# 2_-PHY.net
KiCad netlist of a schematic drawn in Altium Designer
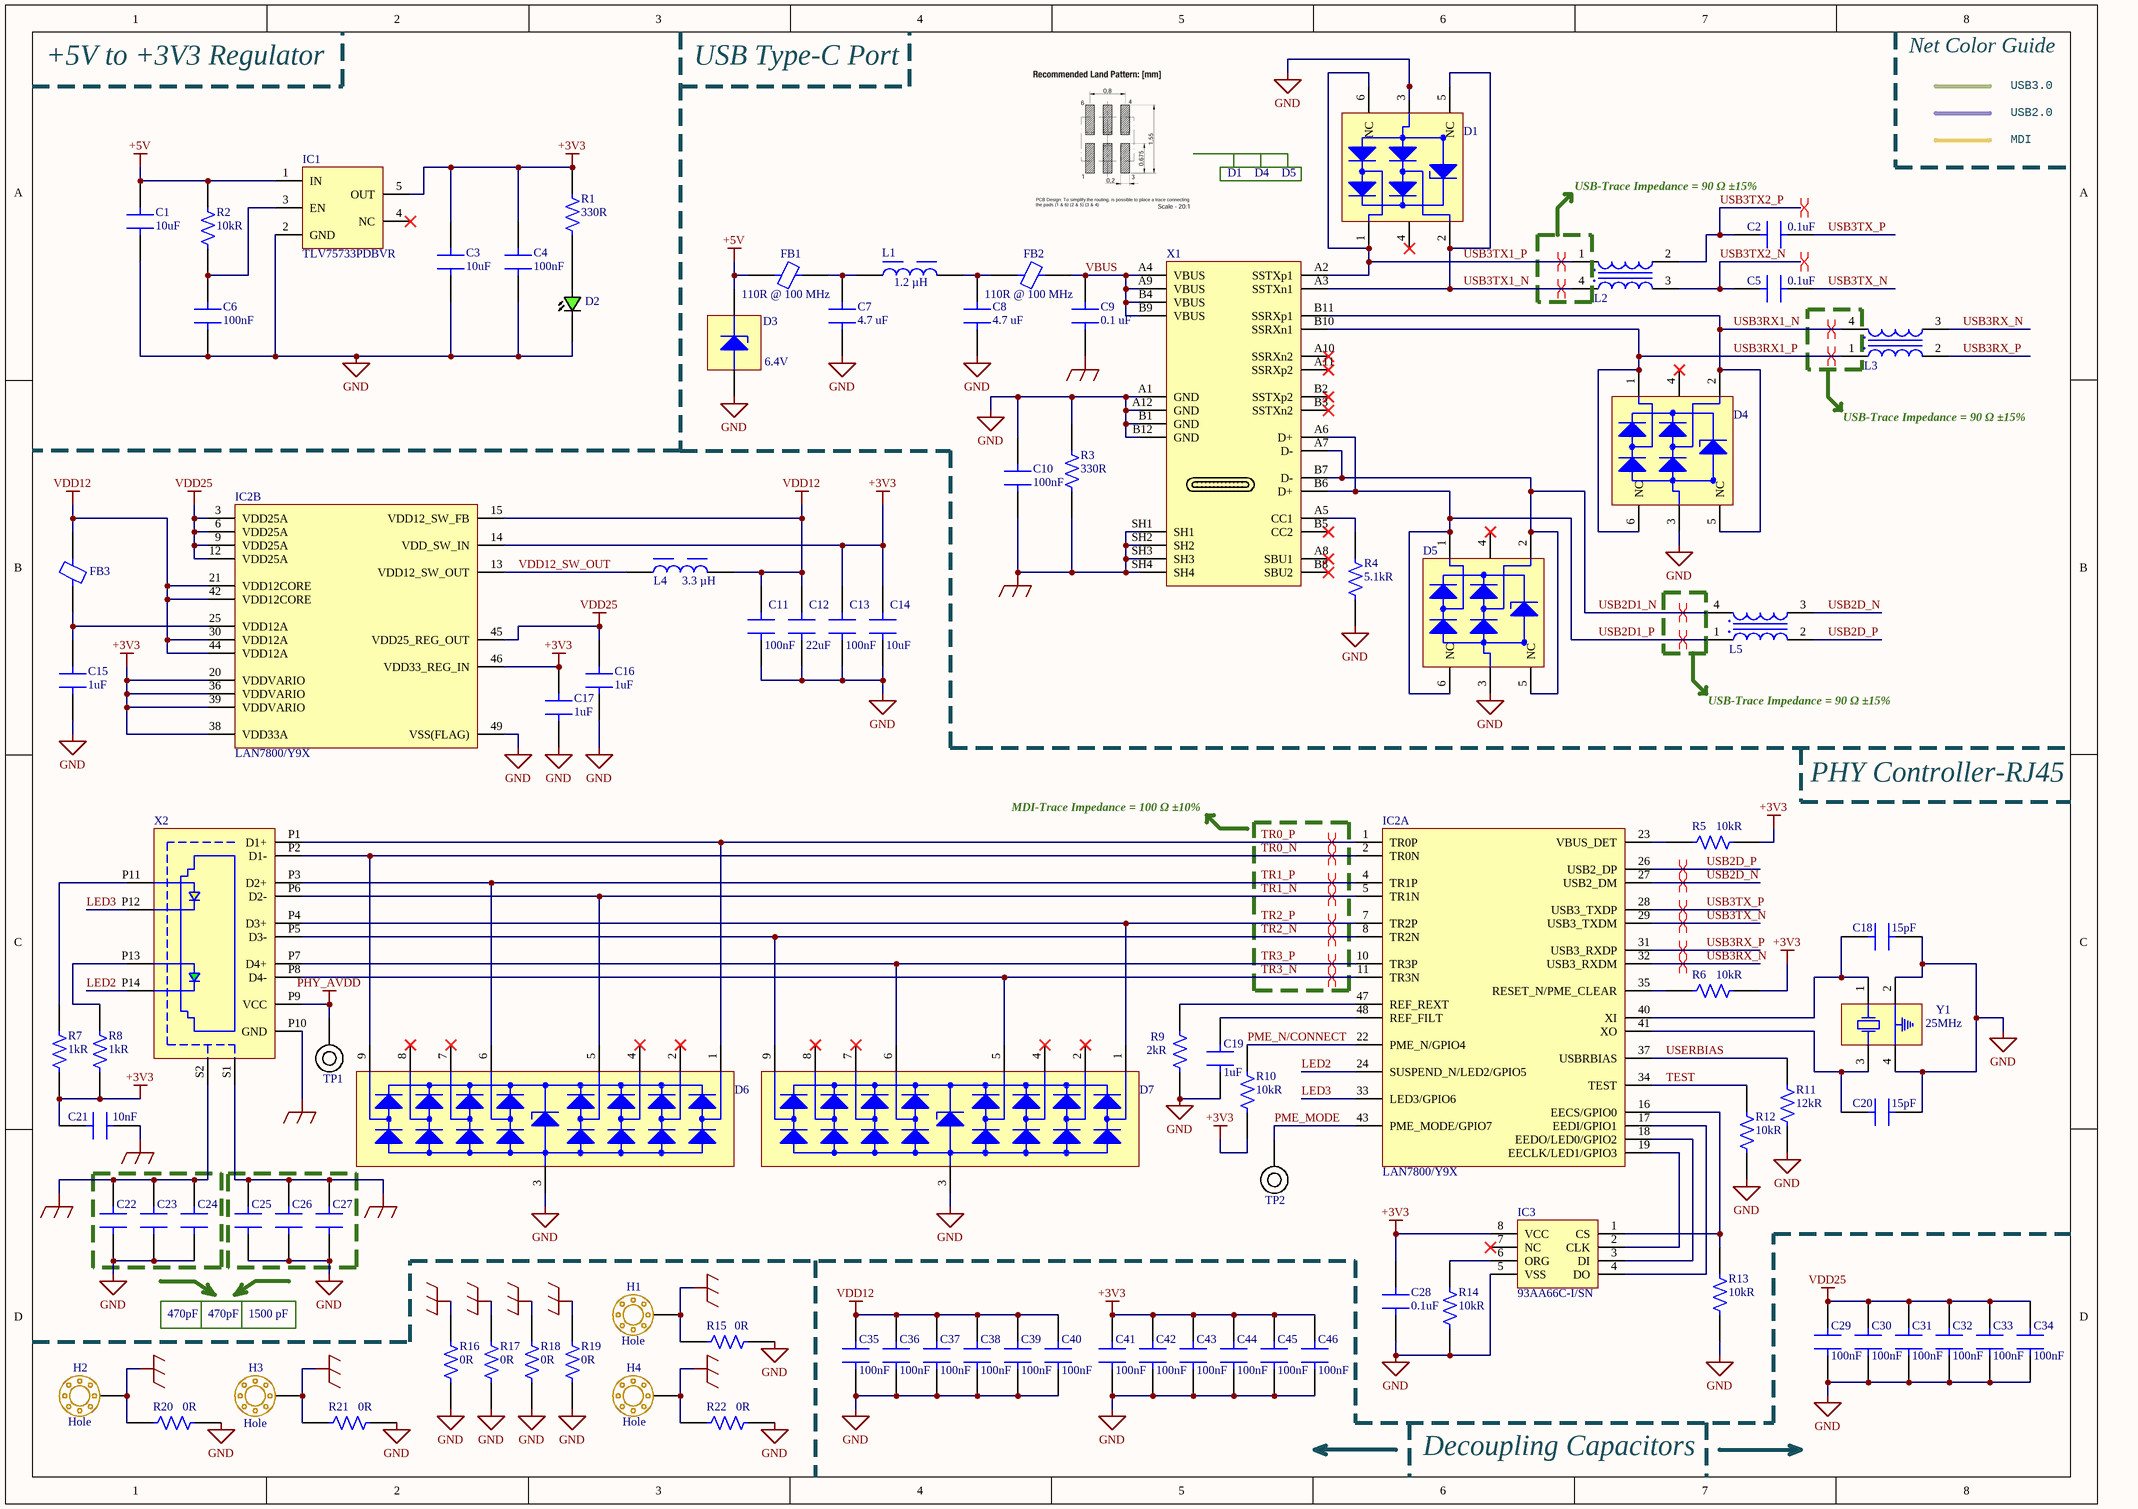
[diagram p0: [2]-PHY.SchDoc]

(export (version "E")
  (design (tool "Eeschema 10.0.6"))
  (components
    (comp (ref "C1")
      (value "GRM188R61A106ME69D")
      (footprint "CAP CER 0603 MURATA")
      (description "10 µF ±20% 10V Ceramic Capacitor X5R 0603 (1608 Metric)")
      (fields
        (field (name "MANUFACTURER") "Murata Electronics")
        (field (name "TOLERANCE") "±20%")
        (field (name "CAPACITANCE") "10uF")
        (field (name "DESIGNED BY") "ADAK")
      )
      (libsource (lib "Project_Library") (part "CAP CER 10UF 10V"))
    )
    (comp (ref "C2")
      (value "885012105018")
      (footprint "CAP CER 0402 (1005 Metric)")
      (description "0.1 µF ±20% 25V Ceramic Capacitor X5R 0402 (1005 Metric)")
      (fields
        (field (name "MANUFACTURER") "Würth Elektronik")
        (field (name "TOLERANCE") "±20%")
        (field (name "CAPACITANCE") "0.1uF")
        (field (name "DESIGNED BY") "ADAK")
      )
      (libsource (lib "Project_Library") (part "CAP CER 0.1UF 25V 0402"))
    )
    (comp (ref "C3")
      (value "GRM188R61A106ME69D")
      (footprint "CAP CER 0603 MURATA")
      (description "10 µF ±20% 10V Ceramic Capacitor X5R 0603 (1608 Metric)")
      (fields
        (field (name "MANUFACTURER") "Murata Electronics")
        (field (name "TOLERANCE") "±20%")
        (field (name "CAPACITANCE") "10uF")
        (field (name "DESIGNED BY") "ADAK")
      )
      (libsource (lib "Project_Library") (part "CAP CER 10UF 10V"))
    )
    (comp (ref "C4")
      (value "885012206071")
      (footprint "CAP CER 0603 (1608 Metric)")
      (description "0.1 µF ±10% 25V Ceramic Capacitor X7R 0603 (1608 Metric)")
      (fields
        (field (name "MANUFACTURER") "Würth Elektronik")
        (field (name "TOLERANCE") "±10%")
        (field (name "CAPACITANCE") "100nF")
        (field (name "DESIGNED BY") "ADAK")
      )
      (libsource (lib "Project_Library") (part "CAP CER 0.1UF 25V"))
    )
    (comp (ref "C5")
      (value "885012105018")
      (footprint "CAP CER 0402 (1005 Metric)")
      (description "0.1 µF ±20% 25V Ceramic Capacitor X5R 0402 (1005 Metric)")
      (fields
        (field (name "MANUFACTURER") "Würth Elektronik")
        (field (name "TOLERANCE") "±20%")
        (field (name "CAPACITANCE") "0.1uF")
        (field (name "DESIGNED BY") "ADAK")
      )
      (libsource (lib "Project_Library") (part "CAP CER 0.1UF 25V 0402"))
    )
    (comp (ref "C6")
      (value "885012206071")
      (footprint "CAP CER 0603 (1608 Metric)")
      (description "0.1 µF ±10% 25V Ceramic Capacitor X7R 0603 (1608 Metric)")
      (fields
        (field (name "MANUFACTURER") "Würth Elektronik")
        (field (name "TOLERANCE") "±10%")
        (field (name "CAPACITANCE") "100nF")
        (field (name "DESIGNED BY") "ADAK")
      )
      (libsource (lib "Project_Library") (part "CAP CER 0.1UF 25V"))
    )
    (comp (ref "C7")
      (value "885012107018")
      (footprint "CAP CER 0805 (2012 Metric)")
      (description "4.7 µF ±20% 25V Ceramic Capacitor X5R 0805 (2012 Metric)")
      (fields
        (field (name "MANUFACTURER") "Würth Elektronik")
        (field (name "TOLERANCE") "±20%")
        (field (name "CAPACITANCE") "4.7 uF")
        (field (name "DESIGNED BY") "ADAK")
      )
      (libsource (lib "Project_Library") (part "CAP CER 4.7UF 25V"))
    )
    (comp (ref "C8")
      (value "885012107018")
      (footprint "CAP CER 0805 (2012 Metric)")
      (description "4.7 µF ±20% 25V Ceramic Capacitor X5R 0805 (2012 Metric)")
      (fields
        (field (name "MANUFACTURER") "Würth Elektronik")
        (field (name "TOLERANCE") "±20%")
        (field (name "CAPACITANCE") "4.7 uF")
        (field (name "DESIGNED BY") "ADAK")
      )
      (libsource (lib "Project_Library") (part "CAP CER 4.7UF 25V"))
    )
    (comp (ref "C9")
      (value "885012207098")
      (footprint "CAP CER 0805 (2012 Metric)")
      (description "0.1 µF ±10% 50V Ceramic Capacitor X7R 0805 (2012 Metric)")
      (fields
        (field (name "MANUFACTURER") "Würth Elektronik")
        (field (name "TOLERANCE") "±10%")
        (field (name "CAPACITANCE") "0.1 uF")
        (field (name "DESIGNED BY") "ADAK")
      )
      (libsource (lib "Project_Library") (part "CAP CER 0.1UF 50V"))
    )
    (comp (ref "C10")
      (value "885012206071")
      (footprint "CAP CER 0603 (1608 Metric)")
      (description "0.1 µF ±10% 25V Ceramic Capacitor X7R 0603 (1608 Metric)")
      (fields
        (field (name "MANUFACTURER") "Würth Elektronik")
        (field (name "TOLERANCE") "±10%")
        (field (name "CAPACITANCE") "100nF")
        (field (name "DESIGNED BY") "ADAK")
      )
      (libsource (lib "Project_Library") (part "CAP CER 0.1UF 25V"))
    )
    (comp (ref "C11")
      (value "885012206071")
      (footprint "CAP CER 0603 (1608 Metric)")
      (description "0.1 µF ±10% 25V Ceramic Capacitor X7R 0603 (1608 Metric)")
      (fields
        (field (name "MANUFACTURER") "Würth Elektronik")
        (field (name "TOLERANCE") "±10%")
        (field (name "CAPACITANCE") "100nF")
        (field (name "DESIGNED BY") "ADAK")
      )
      (libsource (lib "Project_Library") (part "CAP CER 0.1UF 25V"))
    )
    (comp (ref "C12")
      (value "885012107005")
      (footprint "CAP CER 0805 (2012 Metric)")
      (description "22 µF ±20% 6.3V Ceramic Capacitor X5R 0805 (2012 Metric)")
      (fields
        (field (name "MANUFACTURER") "Würth Elektronik")
        (field (name "TOLERANCE") "±20%")
        (field (name "CAPACITANCE") "22uF")
        (field (name "DESIGNED BY") "ADAK")
      )
      (libsource (lib "Project_Library") (part "CAP CER 22UF 6.3V"))
    )
    (comp (ref "C13")
      (value "885012206071")
      (footprint "CAP CER 0603 (1608 Metric)")
      (description "0.1 µF ±10% 25V Ceramic Capacitor X7R 0603 (1608 Metric)")
      (fields
        (field (name "MANUFACTURER") "Würth Elektronik")
        (field (name "TOLERANCE") "±10%")
        (field (name "CAPACITANCE") "100nF")
        (field (name "DESIGNED BY") "ADAK")
      )
      (libsource (lib "Project_Library") (part "CAP CER 0.1UF 25V"))
    )
    (comp (ref "C14")
      (value "GRM188R61A106ME69D")
      (footprint "CAP CER 0603 MURATA")
      (description "10 µF ±20% 10V Ceramic Capacitor X5R 0603 (1608 Metric)")
      (fields
        (field (name "MANUFACTURER") "Murata Electronics")
        (field (name "TOLERANCE") "±20%")
        (field (name "CAPACITANCE") "10uF")
        (field (name "DESIGNED BY") "ADAK")
      )
      (libsource (lib "Project_Library") (part "CAP CER 10UF 10V"))
    )
    (comp (ref "C15")
      (value "885012206052")
      (footprint "CAP CER 0603 (1608 Metric)")
      (description "1 µF ±10% 16V Ceramic Capacitor X7R 0603 (1608 Metric)")
      (fields
        (field (name "MANUFACTURER") "Würth Elektronik")
        (field (name "TOLERANCE") "±10%")
        (field (name "CAPACITANCE") "1uF")
        (field (name "DESIGNED BY") "ADAK")
      )
      (libsource (lib "Project_Library") (part "CAP CER 1UF 16V 0603"))
    )
    (comp (ref "C16")
      (value "885012206052")
      (footprint "CAP CER 0603 (1608 Metric)")
      (description "1 µF ±10% 16V Ceramic Capacitor X7R 0603 (1608 Metric)")
      (fields
        (field (name "MANUFACTURER") "Würth Elektronik")
        (field (name "TOLERANCE") "±10%")
        (field (name "CAPACITANCE") "1uF")
        (field (name "DESIGNED BY") "ADAK")
      )
      (libsource (lib "Project_Library") (part "CAP CER 1UF 16V 0603"))
    )
    (comp (ref "C17")
      (value "885012206052")
      (footprint "CAP CER 0603 (1608 Metric)")
      (description "1 µF ±10% 16V Ceramic Capacitor X7R 0603 (1608 Metric)")
      (fields
        (field (name "MANUFACTURER") "Würth Elektronik")
        (field (name "TOLERANCE") "±10%")
        (field (name "CAPACITANCE") "1uF")
        (field (name "DESIGNED BY") "ADAK")
      )
      (libsource (lib "Project_Library") (part "CAP CER 1UF 16V 0603"))
    )
    (comp (ref "C18")
      (value "885012005056")
      (footprint "CAP CER 0402 (1005 Metric)")
      (description "15 pF ±5% 50V Ceramic Capacitor C0G, NP0 0402 (1005 Metric)")
      (fields
        (field (name "MANUFACTURER") "Würth Elektronik")
        (field (name "TOLERANCE") "±5%")
        (field (name "CAPACITANCE") "15pF")
        (field (name "DESIGNED BY") "ADAK")
      )
      (libsource (lib "Project_Library") (part "CAP CER 15PF 50V"))
    )
    (comp (ref "C19")
      (value "885012206052")
      (footprint "CAP CER 0603 (1608 Metric)")
      (description "1 µF ±10% 16V Ceramic Capacitor X7R 0603 (1608 Metric)")
      (fields
        (field (name "MANUFACTURER") "Würth Elektronik")
        (field (name "TOLERANCE") "±10%")
        (field (name "CAPACITANCE") "1uF")
        (field (name "DESIGNED BY") "ADAK")
      )
      (libsource (lib "Project_Library") (part "CAP CER 1UF 16V 0603"))
    )
    (comp (ref "C20")
      (value "885012005056")
      (footprint "CAP CER 0402 (1005 Metric)")
      (description "15 pF ±5% 50V Ceramic Capacitor C0G, NP0 0402 (1005 Metric)")
      (fields
        (field (name "MANUFACTURER") "Würth Elektronik")
        (field (name "TOLERANCE") "±5%")
        (field (name "CAPACITANCE") "15pF")
        (field (name "DESIGNED BY") "ADAK")
      )
      (libsource (lib "Project_Library") (part "CAP CER 15PF 50V"))
    )
    (comp (ref "C21")
      (value "885012206065")
      (footprint "CAP CER 0603 (1608 Metric)")
      (description "10000 pF ±10% 25V Ceramic Capacitor X7R 0603 (1608 Metric)")
      (fields
        (field (name "MANUFACTURER") "Würth Elektronik")
        (field (name "TOLERANCE") "±10%")
        (field (name "CAPACITANCE") "10nF")
        (field (name "DESIGNED BY") "ADAK")
      )
      (libsource (lib "Project_Library") (part "CAP CER 10000PF 25V"))
    )
    (comp (ref "C22")
      (value "885342208023")
      (footprint "CAP CER 1206 (3216 Metric)")
      (description "470 pF ±10% 2000V (2kV) Ceramic Capacitor X7R 1206 (3216 Metric)")
      (fields
        (field (name "MANUFACTURER") "Würth Elektronik")
        (field (name "TOLERANCE") "±10%")
        (field (name "CAPACITANCE") "470pF")
        (field (name "DESIGNED BY") "ADAK")
      )
      (libsource (lib "Project_Library") (part "CAP CER 470PF 2000V"))
    )
    (comp (ref "C23")
      (value "885342208023")
      (footprint "CAP CER 1206 (3216 Metric)")
      (description "470 pF ±10% 2000V (2kV) Ceramic Capacitor X7R 1206 (3216 Metric)")
      (fields
        (field (name "MANUFACTURER") "Würth Elektronik")
        (field (name "TOLERANCE") "±10%")
        (field (name "CAPACITANCE") "470pF")
        (field (name "DESIGNED BY") "ADAK")
      )
      (libsource (lib "Project_Library") (part "CAP CER 470PF 2000V"))
    )
    (comp (ref "C24")
      (value "HV1825Y152KXMATHV")
      (footprint "CAP CER 1825 (4564 Metric)")
      (description "CAP CER 1500PF 5KV X7R 1825")
      (fields
        (field (name "MANUFACTURER") "Vishay Vitramon")
        (field (name "TOLERANCE") "±10%")
        (field (name "CAPACITANCE") "1500 pF")
        (field (name "DESIGNED BY") "ADAK")
      )
      (libsource (lib "Project_Library") (part "CAP CER 1500PF 5KV"))
    )
    (comp (ref "C25")
      (value "885342208023")
      (footprint "CAP CER 1206 (3216 Metric)")
      (description "470 pF ±10% 2000V (2kV) Ceramic Capacitor X7R 1206 (3216 Metric)")
      (fields
        (field (name "MANUFACTURER") "Würth Elektronik")
        (field (name "TOLERANCE") "±10%")
        (field (name "DESIGNED BY") "ADAK")
      )
      (libsource (lib "Project_Library") (part "CAP CER 470PF 2000V"))
    )
    (comp (ref "C26")
      (value "885342208023")
      (footprint "CAP CER 1206 (3216 Metric)")
      (description "470 pF ±10% 2000V (2kV) Ceramic Capacitor X7R 1206 (3216 Metric)")
      (fields
        (field (name "MANUFACTURER") "Würth Elektronik")
        (field (name "TOLERANCE") "±10%")
        (field (name "DESIGNED BY") "ADAK")
      )
      (libsource (lib "Project_Library") (part "CAP CER 470PF 2000V"))
    )
    (comp (ref "C27")
      (value "HV1825Y152KXMATHV")
      (footprint "CAP CER 1825 (4564 Metric)")
      (description "CAP CER 1500PF 5KV X7R 1825")
      (fields
        (field (name "MANUFACTURER") "Vishay Vitramon")
        (field (name "TOLERANCE") "±10%")
        (field (name "DESIGNED BY") "ADAK")
      )
      (libsource (lib "Project_Library") (part "CAP CER 1500PF 5KV"))
    )
    (comp (ref "C28")
      (value "885012206071")
      (footprint "CAP CER 0603 (1608 Metric)")
      (description "0.1 µF ±10% 25V Ceramic Capacitor X7R 0603 (1608 Metric)")
      (fields
        (field (name "MANUFACTURER") "Würth Elektronik")
        (field (name "TOLERANCE") "±10%")
        (field (name "CAPACITANCE") "0.1uF")
        (field (name "DESIGNED BY") "ADAK")
      )
      (libsource (lib "Project_Library") (part "CAP CER 0.1UF 25V"))
    )
    (comp (ref "C29")
      (value "885012206071")
      (footprint "CAP CER 0603 (1608 Metric)")
      (description "0.1 µF ±10% 25V Ceramic Capacitor X7R 0603 (1608 Metric)")
      (fields
        (field (name "MANUFACTURER") "Würth Elektronik")
        (field (name "TOLERANCE") "±10%")
        (field (name "CAPACITANCE") "100nF")
        (field (name "DESIGNED BY") "ADAK")
      )
      (libsource (lib "Project_Library") (part "CAP CER 0.1UF 25V"))
    )
    (comp (ref "C30")
      (value "885012206071")
      (footprint "CAP CER 0603 (1608 Metric)")
      (description "0.1 µF ±10% 25V Ceramic Capacitor X7R 0603 (1608 Metric)")
      (fields
        (field (name "MANUFACTURER") "Würth Elektronik")
        (field (name "TOLERANCE") "±10%")
        (field (name "CAPACITANCE") "100nF")
        (field (name "DESIGNED BY") "ADAK")
      )
      (libsource (lib "Project_Library") (part "CAP CER 0.1UF 25V"))
    )
    (comp (ref "C31")
      (value "885012206071")
      (footprint "CAP CER 0603 (1608 Metric)")
      (description "0.1 µF ±10% 25V Ceramic Capacitor X7R 0603 (1608 Metric)")
      (fields
        (field (name "MANUFACTURER") "Würth Elektronik")
        (field (name "TOLERANCE") "±10%")
        (field (name "CAPACITANCE") "100nF")
        (field (name "DESIGNED BY") "ADAK")
      )
      (libsource (lib "Project_Library") (part "CAP CER 0.1UF 25V"))
    )
    (comp (ref "C32")
      (value "885012206071")
      (footprint "CAP CER 0603 (1608 Metric)")
      (description "0.1 µF ±10% 25V Ceramic Capacitor X7R 0603 (1608 Metric)")
      (fields
        (field (name "MANUFACTURER") "Würth Elektronik")
        (field (name "TOLERANCE") "±10%")
        (field (name "CAPACITANCE") "100nF")
        (field (name "DESIGNED BY") "ADAK")
      )
      (libsource (lib "Project_Library") (part "CAP CER 0.1UF 25V"))
    )
    (comp (ref "C33")
      (value "885012206071")
      (footprint "CAP CER 0603 (1608 Metric)")
      (description "0.1 µF ±10% 25V Ceramic Capacitor X7R 0603 (1608 Metric)")
      (fields
        (field (name "MANUFACTURER") "Würth Elektronik")
        (field (name "TOLERANCE") "±10%")
        (field (name "CAPACITANCE") "100nF")
        (field (name "DESIGNED BY") "ADAK")
      )
      (libsource (lib "Project_Library") (part "CAP CER 0.1UF 25V"))
    )
    (comp (ref "C34")
      (value "885012206071")
      (footprint "CAP CER 0603 (1608 Metric)")
      (description "0.1 µF ±10% 25V Ceramic Capacitor X7R 0603 (1608 Metric)")
      (fields
        (field (name "MANUFACTURER") "Würth Elektronik")
        (field (name "TOLERANCE") "±10%")
        (field (name "CAPACITANCE") "100nF")
        (field (name "DESIGNED BY") "ADAK")
      )
      (libsource (lib "Project_Library") (part "CAP CER 0.1UF 25V"))
    )
    (comp (ref "C35")
      (value "885012206071")
      (footprint "CAP CER 0603 (1608 Metric)")
      (description "0.1 µF ±10% 25V Ceramic Capacitor X7R 0603 (1608 Metric)")
      (fields
        (field (name "MANUFACTURER") "Würth Elektronik")
        (field (name "TOLERANCE") "±10%")
        (field (name "CAPACITANCE") "100nF")
        (field (name "DESIGNED BY") "ADAK")
      )
      (libsource (lib "Project_Library") (part "CAP CER 0.1UF 25V"))
    )
    (comp (ref "C36")
      (value "885012206071")
      (footprint "CAP CER 0603 (1608 Metric)")
      (description "0.1 µF ±10% 25V Ceramic Capacitor X7R 0603 (1608 Metric)")
      (fields
        (field (name "MANUFACTURER") "Würth Elektronik")
        (field (name "TOLERANCE") "±10%")
        (field (name "CAPACITANCE") "100nF")
        (field (name "DESIGNED BY") "ADAK")
      )
      (libsource (lib "Project_Library") (part "CAP CER 0.1UF 25V"))
    )
    (comp (ref "C37")
      (value "885012206071")
      (footprint "CAP CER 0603 (1608 Metric)")
      (description "0.1 µF ±10% 25V Ceramic Capacitor X7R 0603 (1608 Metric)")
      (fields
        (field (name "MANUFACTURER") "Würth Elektronik")
        (field (name "TOLERANCE") "±10%")
        (field (name "CAPACITANCE") "100nF")
        (field (name "DESIGNED BY") "ADAK")
      )
      (libsource (lib "Project_Library") (part "CAP CER 0.1UF 25V"))
    )
    (comp (ref "C38")
      (value "885012206071")
      (footprint "CAP CER 0603 (1608 Metric)")
      (description "0.1 µF ±10% 25V Ceramic Capacitor X7R 0603 (1608 Metric)")
      (fields
        (field (name "MANUFACTURER") "Würth Elektronik")
        (field (name "TOLERANCE") "±10%")
        (field (name "CAPACITANCE") "100nF")
        (field (name "DESIGNED BY") "ADAK")
      )
      (libsource (lib "Project_Library") (part "CAP CER 0.1UF 25V"))
    )
    (comp (ref "C39")
      (value "885012206071")
      (footprint "CAP CER 0603 (1608 Metric)")
      (description "0.1 µF ±10% 25V Ceramic Capacitor X7R 0603 (1608 Metric)")
      (fields
        (field (name "MANUFACTURER") "Würth Elektronik")
        (field (name "TOLERANCE") "±10%")
        (field (name "CAPACITANCE") "100nF")
        (field (name "DESIGNED BY") "ADAK")
      )
      (libsource (lib "Project_Library") (part "CAP CER 0.1UF 25V"))
    )
    (comp (ref "C40")
      (value "885012206071")
      (footprint "CAP CER 0603 (1608 Metric)")
      (description "0.1 µF ±10% 25V Ceramic Capacitor X7R 0603 (1608 Metric)")
      (fields
        (field (name "MANUFACTURER") "Würth Elektronik")
        (field (name "TOLERANCE") "±10%")
        (field (name "CAPACITANCE") "100nF")
        (field (name "DESIGNED BY") "ADAK")
      )
      (libsource (lib "Project_Library") (part "CAP CER 0.1UF 25V"))
    )
    (comp (ref "C41")
      (value "885012206071")
      (footprint "CAP CER 0603 (1608 Metric)")
      (description "0.1 µF ±10% 25V Ceramic Capacitor X7R 0603 (1608 Metric)")
      (fields
        (field (name "MANUFACTURER") "Würth Elektronik")
        (field (name "TOLERANCE") "±10%")
        (field (name "CAPACITANCE") "100nF")
        (field (name "DESIGNED BY") "ADAK")
      )
      (libsource (lib "Project_Library") (part "CAP CER 0.1UF 25V"))
    )
    (comp (ref "C42")
      (value "885012206071")
      (footprint "CAP CER 0603 (1608 Metric)")
      (description "0.1 µF ±10% 25V Ceramic Capacitor X7R 0603 (1608 Metric)")
      (fields
        (field (name "MANUFACTURER") "Würth Elektronik")
        (field (name "TOLERANCE") "±10%")
        (field (name "CAPACITANCE") "100nF")
        (field (name "DESIGNED BY") "ADAK")
      )
      (libsource (lib "Project_Library") (part "CAP CER 0.1UF 25V"))
    )
    (comp (ref "C43")
      (value "885012206071")
      (footprint "CAP CER 0603 (1608 Metric)")
      (description "0.1 µF ±10% 25V Ceramic Capacitor X7R 0603 (1608 Metric)")
      (fields
        (field (name "MANUFACTURER") "Würth Elektronik")
        (field (name "TOLERANCE") "±10%")
        (field (name "CAPACITANCE") "100nF")
        (field (name "DESIGNED BY") "ADAK")
      )
      (libsource (lib "Project_Library") (part "CAP CER 0.1UF 25V"))
    )
    (comp (ref "C44")
      (value "885012206071")
      (footprint "CAP CER 0603 (1608 Metric)")
      (description "0.1 µF ±10% 25V Ceramic Capacitor X7R 0603 (1608 Metric)")
      (fields
        (field (name "MANUFACTURER") "Würth Elektronik")
        (field (name "TOLERANCE") "±10%")
        (field (name "CAPACITANCE") "100nF")
        (field (name "DESIGNED BY") "ADAK")
      )
      (libsource (lib "Project_Library") (part "CAP CER 0.1UF 25V"))
    )
    (comp (ref "C45")
      (value "885012206071")
      (footprint "CAP CER 0603 (1608 Metric)")
      (description "0.1 µF ±10% 25V Ceramic Capacitor X7R 0603 (1608 Metric)")
      (fields
        (field (name "MANUFACTURER") "Würth Elektronik")
        (field (name "TOLERANCE") "±10%")
        (field (name "CAPACITANCE") "100nF")
        (field (name "DESIGNED BY") "ADAK")
      )
      (libsource (lib "Project_Library") (part "CAP CER 0.1UF 25V"))
    )
    (comp (ref "C46")
      (value "885012206071")
      (footprint "CAP CER 0603 (1608 Metric)")
      (description "0.1 µF ±10% 25V Ceramic Capacitor X7R 0603 (1608 Metric)")
      (fields
        (field (name "MANUFACTURER") "Würth Elektronik")
        (field (name "TOLERANCE") "±10%")
        (field (name "CAPACITANCE") "100nF")
        (field (name "DESIGNED BY") "ADAK")
      )
      (libsource (lib "Project_Library") (part "CAP CER 0.1UF 25V"))
    )
    (comp (ref "D1")
      (value "824012823")
      (footprint "6-XFDFN")
      (description "TVS DIODE 3.3VWM 13VC DFN1210-6")
      (fields (field (name "MANUFACTURER") "Würth Elektronik") (field (name "DESIGNED BY") "ADAK"))
      (libsource (lib "") (part "TVS DIODE 3.3VWM_1"))
    )
    (comp (ref "D2")
      (value "150060VS75020")
      (footprint "LED GREEN 0603")
      (description "LED GREEN CLEAR 0603 SMD")
      (fields (field (name "MANUFACTURER") "Würth Elektronik") (field (name "DESIGNED BY") "ADAK"))
      (libsource (lib "Project_Library") (part "LED GREEN 0603"))
    )
    (comp (ref "D3")
      (value "ESDA7P60-1U1M")
      (footprint "2-UDFN")
      (description "TVS DIODE 5VWM 11.6VC 1610")
      (fields
        (field (name "MANUFACTURER") "STMicroelectronics")
        (field (name "VOLTAGE - BREAKDOWN (MIN)") "6.4V")
        (field (name "DESIGNED BY") "ADAK")
      )
      (libsource (lib "Project_Library") (part "TVS DIODE 5VWM 11.6VC"))
    )
    (comp (ref "D4")
      (value "824012823")
      (footprint "6-XFDFN")
      (description "TVS DIODE 3.3VWM 13VC DFN1210-6")
      (fields (field (name "MANUFACTURER") "Würth Elektronik") (field (name "DESIGNED BY") "ADAK"))
      (libsource (lib "Project_Library") (part "TVS DIODE 3.3VWM"))
    )
    (comp (ref "D5")
      (value "824012823")
      (footprint "6-XFDFN")
      (description "TVS DIODE 3.3VWM 13VC DFN1210-6")
      (fields (field (name "MANUFACTURER") "Würth Elektronik") (field (name "DESIGNED BY") "ADAK"))
      (libsource (lib "Project_Library") (part "TVS DIODE 3.3VWM"))
    )
    (comp (ref "D6")
      (value "824014885")
      (footprint "DFN3810-9")
      (description "TVS DIODE 5VWM 10.5VC DFN3810-9")
      (fields (field (name "MANUFACTURER") "Würth Elektronik") (field (name "DESIGNED BY") "ADAK"))
      (libsource (lib "Project_Library") (part "TVS DIODE 5VWM 10.5VC"))
    )
    (comp (ref "D7")
      (value "824014885")
      (footprint "DFN3810-9")
      (description "TVS DIODE 5VWM 10.5VC DFN3810-9")
      (fields (field (name "MANUFACTURER") "Würth Elektronik") (field (name "DESIGNED BY") "ADAK"))
      (libsource (lib "Project_Library") (part "TVS DIODE 5VWM 10.5VC"))
    )
    (comp (ref "FB1")
      (value "74279221111")
      (footprint "FB 1206 (3216 Metric)")
      (description "FERRITE BEAD 110 OHM 1206 1LN")
      (fields
        (field (name "MANUFACTURER") "Würth Elektronik")
        (field (name "IMPEDANCE @ FREQUENCY") "110R @ 100 MHz")
        (field (name "DESIGNED BY") "ADAK")
      )
      (libsource (lib "Project_Library") (part "FERRITE BEAD 110 OHM"))
    )
    (comp (ref "FB2")
      (value "74279221111")
      (footprint "FB 1206 (3216 Metric)")
      (description "FERRITE BEAD 110 OHM 1206 1LN")
      (fields
        (field (name "MANUFACTURER") "Würth Elektronik")
        (field (name "IMPEDANCE @ FREQUENCY") "110R @ 100 MHz")
        (field (name "DESIGNED BY") "ADAK")
      )
      (libsource (lib "Project_Library") (part "FERRITE BEAD 110 OHM"))
    )
    (comp (ref "FB3")
      (value "742792625")
      (footprint "FB 0603 (1608 Metric)")
      (description "FERRITE BEAD 120 OHM 0603 1LN")
      (fields (field (name "MANUFACTURER") "Würth Elektronik") (field (name "DESIGNED BY") "ADAK"))
      (libsource (lib "Project_Library") (part "FERRITE BEAD 120 OHM"))
    )
    (comp (ref "H1")
      (value "Hole")
      (footprint "MOUNTING HOLE")
      (description "Mounting Hole")
      (libsource (lib "Project_Library") (part "Mounting Hole"))
    )
    (comp (ref "H2")
      (value "Hole")
      (footprint "MOUNTING HOLE")
      (description "Mounting Hole")
      (libsource (lib "Project_Library") (part "Mounting Hole"))
    )
    (comp (ref "H3")
      (value "Hole")
      (footprint "MOUNTING HOLE")
      (description "Mounting Hole")
      (libsource (lib "Project_Library") (part "Mounting Hole"))
    )
    (comp (ref "H4")
      (value "Hole")
      (footprint "MOUNTING HOLE")
      (description "Mounting Hole")
      (libsource (lib "Project_Library") (part "Mounting Hole"))
    )
    (comp (ref "IC1")
      (value "TLV75733PDBVR")
      (footprint "SOT-23-5")
      (description "IC REG LINEAR 3.3V 1A SOT23-5")
      (fields
        (field (name "MANUFACTURER") "Texas Instruments")
        (field (name "MANUFACTURER PRODUCT NUMBER") "TLV75733PDBVR")
        (field (name "DESIGNED BY") "ADAK")
      )
      (libsource (lib "Project_Library") (part "TLV75733PDBVR"))
    )
    (comp (ref "IC2")
      (value "LAN7800/Y9X")
      (footprint "48-SQFN (7x7)")
      (description "IC ETHERNET CTLR USB 48SQFN")
      (fields
        (field (name "MANUFACTURER") "Microchip Technology")
        (field (name "MANUFACTURER PRODUCT NUMBER") "LAN7800/Y9X")
        (field (name "DESIGNED BY") "ADAK")
      )
      (libsource (lib "Project_Library") (part "LAN7800/Y9X"))
    )
    (comp (ref "IC3")
      (value "93AA66C-I/SN")
      (footprint "SOIC-8")
      (description "IC EEPROM 4KBIT MICROWIRE 8SOIC")
      (fields
        (field (name "MANUFACTURER") "Microchip Technology")
        (field (name "MANUFACTURER PRODUCT NUMBER") "93AA66C-I/SN")
        (field (name "DESIGNED BY") "ADAK")
      )
      (libsource (lib "Project_Library") (part "IC EEPROM 4KBIT"))
    )
    (comp (ref "L1")
      (value "74438336012")
      (footprint "IND 1212 (3030 Metric)")
      (description "FIXED IND 1.2UH 3.9A 36 MOHM SMD")
      (fields
        (field (name "MANUFACTURER") "Würth Elektronik")
        (field (name "TOLERANCE") "±20%")
        (field (name "INDUCTANCE") "1.2 µH")
        (field (name "DESIGNED BY") "ADAK")
      )
      (libsource (lib "Project_Library") (part "IND 1.2UH"))
    )
    (comp (ref "L2")
      (value "7442335600")
      (footprint "CMC (1.20mm x 1.00mm), 4 PC Pad")
      (description "CMC 600MA 2LN 60OHM SMD AEC-Q200")
      (fields (field (name "MANUFACTURER") "Würth Elektronik") (field (name "DESIGNED BY") "ADAK"))
      (libsource (lib "") (part "CMC 60OHM_1"))
    )
    (comp (ref "L3")
      (value "7442335600")
      (footprint "CMC (1.20mm x 1.00mm), 4 PC Pad")
      (description "CMC 600MA 2LN 60OHM SMD AEC-Q200")
      (fields (field (name "MANUFACTURER") "Würth Elektronik") (field (name "DESIGNED BY") "ADAK"))
      (libsource (lib "Project_Library") (part "CMC 60OHM"))
    )
    (comp (ref "L4")
      (value "74404032033")
      (footprint "IND Nonstandard")
      (description "FIXED IND 3.3UH 1.5A 70 MOHM SMD")
      (fields
        (field (name "MANUFACTURER") "Würth Elektronik")
        (field (name "TOLERANCE") "±20%")
        (field (name "INDUCTANCE") "3.3 µH")
        (field (name "DESIGNED BY") "ADAK")
      )
      (libsource (lib "Project_Library") (part "IND 3.3UH"))
    )
    (comp (ref "L5")
      (value "744232090")
      (footprint "CMC (3.20mm x 1.60mm),4 PC Pad")
      (description "CMC 370MA 2LN 90OHM SMD AEC-Q200")
      (fields (field (name "MANUFACTURER") "Würth Elektronik") (field (name "DESIGNED BY") "ADAK"))
      (libsource (lib "Project_Library") (part "CMC  90OHM"))
    )
    (comp (ref "R1")
      (value "RC0603FR-07330RL")
      (footprint "RES 0603 SMD")
      (description "330 Ohms ±1% 0.1W, 1/10W Chip Resistor 0603 (1608 Metric) Moisture Resistant Thick Film")
      (fields
        (field (name "MANUFACTURER") "YAGEO")
        (field (name "TOLERANCE") "±1%")
        (field (name "RESISTANCE") "330R")
        (field (name "DESIGNED BY") "ADAK")
      )
      (libsource (lib "Project_Library") (part "RES 330 OHM 0603"))
    )
    (comp (ref "R2")
      (value "RC0603FR-0710KL")
      (footprint "RES 0603 SMD")
      (description "10 kOhms ±1% 0.1W, 1/10W Chip Resistor 0603 (1608 Metric) Moisture Resistant Thick Film")
      (fields
        (field (name "MANUFACTURER") "YAGEO")
        (field (name "TOLERANCE") "±1%")
        (field (name "RESISTANCE") "10kR")
        (field (name "DESIGNED BY") "ADAK")
      )
      (libsource (lib "Project_Library") (part "RES 10K OHM 0603"))
    )
    (comp (ref "R3")
      (value "RC0603FR-07330RL")
      (footprint "RES 0603 SMD")
      (description "330 Ohms ±1% 0.1W, 1/10W Chip Resistor 0603 (1608 Metric) Moisture Resistant Thick Film")
      (fields
        (field (name "MANUFACTURER") "YAGEO")
        (field (name "TOLERANCE") "±1%")
        (field (name "RESISTANCE") "330R")
        (field (name "DESIGNED BY") "ADAK")
      )
      (libsource (lib "Project_Library") (part "RES 330 OHM 0603"))
    )
    (comp (ref "R4")
      (value "RC0603FR-075K1L")
      (footprint "RES 0603 SMD")
      (description "5.1 kOhms ±1% 0.1W, 1/10W Chip Resistor 0603 (1608 Metric) Moisture Resistant Thick Film")
      (fields
        (field (name "MANUFACTURER") "YAGEO")
        (field (name "TOLERANCE") "±1%")
        (field (name "RESISTANCE") "5.1kR")
        (field (name "DESIGNED BY") "ADAK")
      )
      (libsource (lib "Project_Library") (part "RES 5K1 OHM 0603"))
    )
    (comp (ref "R5")
      (value "RC0603FR-0710KL")
      (footprint "RES 0603 SMD")
      (description "10 kOhms ±1% 0.1W, 1/10W Chip Resistor 0603 (1608 Metric) Moisture Resistant Thick Film")
      (fields
        (field (name "MANUFACTURER") "YAGEO")
        (field (name "TOLERANCE") "±1%")
        (field (name "RESISTANCE") "10kR")
        (field (name "DESIGNED BY") "ADAK")
      )
      (libsource (lib "Project_Library") (part "RES 10K OHM 0603"))
    )
    (comp (ref "R6")
      (value "RC0603FR-0710KL")
      (footprint "RES 0603 SMD")
      (description "10 kOhms ±1% 0.1W, 1/10W Chip Resistor 0603 (1608 Metric) Moisture Resistant Thick Film")
      (fields
        (field (name "MANUFACTURER") "YAGEO")
        (field (name "TOLERANCE") "±1%")
        (field (name "RESISTANCE") "10kR")
        (field (name "DESIGNED BY") "ADAK")
      )
      (libsource (lib "Project_Library") (part "RES 10K OHM 0603"))
    )
    (comp (ref "R7")
      (value "RC0603FR-071KL")
      (footprint "RES 0603 SMD")
      (description "1 kOhms ±1% 0.1W, 1/10W Chip Resistor 0603 (1608 Metric) Moisture Resistant Thick Film")
      (fields
        (field (name "MANUFACTURER") "YAGEO")
        (field (name "TOLERANCE") "±1%")
        (field (name "RESISTANCE") "1kR")
        (field (name "DESIGNED BY") "ADAK")
      )
      (libsource (lib "Project_Library") (part "RES 1K OHM 0603"))
    )
    (comp (ref "R8")
      (value "RC0603FR-071KL")
      (footprint "RES 0603 SMD")
      (description "1 kOhms ±1% 0.1W, 1/10W Chip Resistor 0603 (1608 Metric) Moisture Resistant Thick Film")
      (fields
        (field (name "MANUFACTURER") "YAGEO")
        (field (name "TOLERANCE") "±1%")
        (field (name "RESISTANCE") "1kR")
        (field (name "DESIGNED BY") "ADAK")
      )
      (libsource (lib "Project_Library") (part "RES 1K OHM 0603"))
    )
    (comp (ref "R9")
      (value "RC0603FR-072KL")
      (footprint "RES 0603 SMD")
      (description "2 kOhms ±1% 0.1W, 1/10W Chip Resistor 0603 (1608 Metric) Moisture Resistant Thick Film")
      (fields
        (field (name "MANUFACTURER") "YAGEO")
        (field (name "TOLERANCE") "±1%")
        (field (name "RESISTANCE") "2kR")
        (field (name "DESIGNED BY") "ADAK")
      )
      (libsource (lib "Project_Library") (part "RES 2K OHM 0603"))
    )
    (comp (ref "R10")
      (value "RC0603FR-0710KL")
      (footprint "RES 0603 SMD")
      (description "10 kOhms ±1% 0.1W, 1/10W Chip Resistor 0603 (1608 Metric) Moisture Resistant Thick Film")
      (fields
        (field (name "MANUFACTURER") "YAGEO")
        (field (name "TOLERANCE") "±1%")
        (field (name "RESISTANCE") "10kR")
        (field (name "DESIGNED BY") "ADAK")
      )
      (libsource (lib "Project_Library") (part "RES 10K OHM 0603"))
    )
    (comp (ref "R11")
      (value "RC0603FR-0712KL")
      (footprint "RES 0603 SMD")
      (description "12 kOhms ±1% 0.1W, 1/10W Chip Resistor 0603 (1608 Metric) Moisture Resistant Thick Film")
      (fields
        (field (name "MANUFACTURER") "YAGEO")
        (field (name "TOLERANCE") "±1%")
        (field (name "RESISTANCE") "12kR")
        (field (name "DESIGNED BY") "ADAK")
      )
      (libsource (lib "Project_Library") (part "RES 12K OHM 0603"))
    )
    (comp (ref "R12")
      (value "RC0603FR-0710KL")
      (footprint "RES 0603 SMD")
      (description "10 kOhms ±1% 0.1W, 1/10W Chip Resistor 0603 (1608 Metric) Moisture Resistant Thick Film")
      (fields
        (field (name "MANUFACTURER") "YAGEO")
        (field (name "TOLERANCE") "±1%")
        (field (name "RESISTANCE") "10kR")
        (field (name "DESIGNED BY") "ADAK")
      )
      (libsource (lib "Project_Library") (part "RES 10K OHM 0603"))
    )
    (comp (ref "R13")
      (value "RC0603FR-0710KL")
      (footprint "RES 0603 SMD")
      (description "10 kOhms ±1% 0.1W, 1/10W Chip Resistor 0603 (1608 Metric) Moisture Resistant Thick Film")
      (fields
        (field (name "MANUFACTURER") "YAGEO")
        (field (name "TOLERANCE") "±1%")
        (field (name "RESISTANCE") "10kR")
        (field (name "DESIGNED BY") "ADAK")
      )
      (libsource (lib "Project_Library") (part "RES 10K OHM 0603"))
    )
    (comp (ref "R14")
      (value "RC0603FR-0710KL")
      (footprint "RES 0603 SMD")
      (description "10 kOhms ±1% 0.1W, 1/10W Chip Resistor 0603 (1608 Metric) Moisture Resistant Thick Film")
      (fields
        (field (name "MANUFACTURER") "YAGEO")
        (field (name "TOLERANCE") "±1%")
        (field (name "RESISTANCE") "10kR")
        (field (name "DESIGNED BY") "ADAK")
      )
      (libsource (lib "Project_Library") (part "RES 10K OHM 0603"))
    )
    (comp (ref "R15")
      (value "RC0402FR-070RL")
      (footprint "RES 0402 SMD")
      (description "0 Ohms Jumper Chip Resistor 0402 (1005 Metric) Moisture Resistant Thick Film")
      (fields
        (field (name "MANUFACTURER") "YAGEO")
        (field (name "RESISTANCE") "0R")
        (field (name "DESIGNED BY") "ADAK")
      )
      (libsource (lib "Project_Library") (part "RES 0 OHM 0402"))
    )
    (comp (ref "R16")
      (value "RC0402FR-070RL")
      (footprint "RES 0402 SMD")
      (description "0 Ohms Jumper Chip Resistor 0402 (1005 Metric) Moisture Resistant Thick Film")
      (fields
        (field (name "MANUFACTURER") "YAGEO")
        (field (name "RESISTANCE") "0R")
        (field (name "DESIGNED BY") "ADAK")
      )
      (libsource (lib "Project_Library") (part "RES 0 OHM 0402"))
    )
    (comp (ref "R17")
      (value "RC0402FR-070RL")
      (footprint "RES 0402 SMD")
      (description "0 Ohms Jumper Chip Resistor 0402 (1005 Metric) Moisture Resistant Thick Film")
      (fields
        (field (name "MANUFACTURER") "YAGEO")
        (field (name "RESISTANCE") "0R")
        (field (name "DESIGNED BY") "ADAK")
      )
      (libsource (lib "Project_Library") (part "RES 0 OHM 0402"))
    )
    (comp (ref "R18")
      (value "RC0402FR-070RL")
      (footprint "RES 0402 SMD")
      (description "0 Ohms Jumper Chip Resistor 0402 (1005 Metric) Moisture Resistant Thick Film")
      (fields
        (field (name "MANUFACTURER") "YAGEO")
        (field (name "RESISTANCE") "0R")
        (field (name "DESIGNED BY") "ADAK")
      )
      (libsource (lib "Project_Library") (part "RES 0 OHM 0402"))
    )
    (comp (ref "R19")
      (value "RC0402FR-070RL")
      (footprint "RES 0402 SMD")
      (description "0 Ohms Jumper Chip Resistor 0402 (1005 Metric) Moisture Resistant Thick Film")
      (fields
        (field (name "MANUFACTURER") "YAGEO")
        (field (name "RESISTANCE") "0R")
        (field (name "DESIGNED BY") "ADAK")
      )
      (libsource (lib "Project_Library") (part "RES 0 OHM 0402"))
    )
    (comp (ref "R20")
      (value "RC0402FR-070RL")
      (footprint "RES 0402 SMD")
      (description "0 Ohms Jumper Chip Resistor 0402 (1005 Metric) Moisture Resistant Thick Film")
      (fields
        (field (name "MANUFACTURER") "YAGEO")
        (field (name "RESISTANCE") "0R")
        (field (name "DESIGNED BY") "ADAK")
      )
      (libsource (lib "Project_Library") (part "RES 0 OHM 0402"))
    )
    (comp (ref "R21")
      (value "RC0402FR-070RL")
      (footprint "RES 0402 SMD")
      (description "0 Ohms Jumper Chip Resistor 0402 (1005 Metric) Moisture Resistant Thick Film")
      (fields
        (field (name "MANUFACTURER") "YAGEO")
        (field (name "RESISTANCE") "0R")
        (field (name "DESIGNED BY") "ADAK")
      )
      (libsource (lib "Project_Library") (part "RES 0 OHM 0402"))
    )
    (comp (ref "R22")
      (value "RC0402FR-070RL")
      (footprint "RES 0402 SMD")
      (description "0 Ohms Jumper Chip Resistor 0402 (1005 Metric) Moisture Resistant Thick Film")
      (fields
        (field (name "MANUFACTURER") "YAGEO")
        (field (name "RESISTANCE") "0R")
        (field (name "DESIGNED BY") "ADAK")
      )
      (libsource (lib "Project_Library") (part "RES 0 OHM 0402"))
    )
    (comp (ref "TP1")
      (value "Test Point")
      (footprint "TEST POINT")
      (libsource (lib "Project_Library") (part "Test Point"))
    )
    (comp (ref "TP2")
      (value "Test Point")
      (footprint "TEST POINT")
      (libsource (lib "Project_Library") (part "Test Point"))
    )
    (comp (ref "X1")
      (value "632723300011")
      (footprint "632723300011")
      (description "CONN RCP USB3.1 TYPEC 24P SMD RA")
      (fields (field (name "MANUFACTURER") "Würth Elektronik") (field (name "DESIGNED BY") "ADAK"))
      (libsource (lib "Project_Library") (part "CONN RCP USB3.1 TYPEC"))
    )
    (comp (ref "X2")
      (value "7499111121A")
      (footprint "7499111121A")
      (description "CONN JACK 1PORT 1000 BASE-T PCB")
      (fields (field (name "MANUFACTURER") "Würth Elektronik") (field (name "DESIGNED BY") "ADAK"))
      (libsource (lib "Project_Library") (part "CONN JACK RJ45"))
    )
    (comp (ref "Y1")
      (value "TSX-3225 25.0000MF10P-C3")
      (footprint "TSX-3225 25.0000MF10P-C3")
      (description "CRYSTAL 25.0000MHZ 18PF SMD")
      (fields
        (field (name "MANUFACTURER") "EPSON")
        (field (name "FREQUENCY") "25MHz")
        (field (name "DESIGNED BY") "ADAK")
      )
      (libsource (lib "Project_Library") (part "TSX-3225 25.0000MF10P-C3"))
    )
  )
  (nets
    (net (code "1") (name "+3V3") (class "Default")
      (node (ref "C13") (pin "2") (pinfunction "2_2") (pintype "passive"))
      (node (ref "C14") (pin "2") (pinfunction "2_2") (pintype "passive"))
      (node (ref "C17") (pin "2") (pinfunction "2_2") (pintype "passive"))
      (node (ref "C21") (pin "2") (pinfunction "2_2") (pintype "passive"))
      (node (ref "C28") (pin "2") (pinfunction "2_2") (pintype "passive"))
      (node (ref "C3") (pin "2") (pinfunction "2_2") (pintype "passive"))
      (node (ref "C4") (pin "2") (pinfunction "2_2") (pintype "passive"))
      (node (ref "C41") (pin "2") (pinfunction "2_2") (pintype "passive"))
      (node (ref "C42") (pin "2") (pinfunction "2_2") (pintype "passive"))
      (node (ref "C43") (pin "2") (pinfunction "2_2") (pintype "passive"))
      (node (ref "C44") (pin "2") (pinfunction "2_2") (pintype "passive"))
      (node (ref "C45") (pin "2") (pinfunction "2_2") (pintype "passive"))
      (node (ref "C46") (pin "2") (pinfunction "2_2") (pintype "passive"))
      (node (ref "IC1") (pin "5") (pinfunction "OUT_5") (pintype "passive"))
      (node (ref "IC2") (pin "14") (pinfunction "VDD_SW_IN_14") (pintype "passive"))
      (node (ref "IC2") (pin "20") (pinfunction "VDDVARIO_20") (pintype "passive"))
      (node (ref "IC2") (pin "36") (pinfunction "VDDVARIO_36") (pintype "passive"))
      (node (ref "IC2") (pin "38") (pinfunction "VDD33A_38") (pintype "passive"))
      (node (ref "IC2") (pin "39") (pinfunction "VDDVARIO_39") (pintype "passive"))
      (node (ref "IC2") (pin "46") (pinfunction "VDD33_REG_IN_46") (pintype "passive"))
      (node (ref "IC3") (pin "8") (pinfunction "VCC_8") (pintype "passive"))
      (node (ref "R1") (pin "2") (pinfunction "2_2") (pintype "passive"))
      (node (ref "R10") (pin "1") (pinfunction "1_1") (pintype "passive"))
      (node (ref "R5") (pin "2") (pinfunction "2_2") (pintype "passive"))
      (node (ref "R6") (pin "2") (pinfunction "2_2") (pintype "passive"))
      (node (ref "R7") (pin "1") (pinfunction "1_1") (pintype "passive"))
      (node (ref "R8") (pin "1") (pinfunction "1_1") (pintype "passive"))
    )
    (net (code "2") (name "+5V") (class "Default")
      (node (ref "C1") (pin "2") (pinfunction "2_2") (pintype "passive"))
      (node (ref "D3") (pin "1") (pinfunction "I/O_1") (pintype "passive"))
      (node (ref "FB1") (pin "1") (pinfunction "1_1") (pintype "passive"))
      (node (ref "IC1") (pin "1") (pinfunction "IN_1") (pintype "passive"))
      (node (ref "R2") (pin "2") (pinfunction "2_2") (pintype "passive"))
    )
    (net (code "3") (name "/LED2") (class "Default")
      (node (ref "IC2") (pin "24") (pinfunction "SUSPEND_N/LED2/GPIO5_24") (pintype "passive"))
      (node (ref "X2") (pin "P14") (pinfunction "14_P14") (pintype "passive"))
    )
    (net (code "4") (name "/LED3") (class "Default")
      (node (ref "IC2") (pin "33") (pinfunction "LED3/GPIO6_33") (pintype "passive"))
      (node (ref "X2") (pin "P12") (pinfunction "12_P12") (pintype "passive"))
    )
    (net (code "5") (name "/PME_MODE") (class "Default")
      (node (ref "IC2") (pin "43") (pinfunction "PME_MODE/GPIO7_43") (pintype "passive"))
      (node (ref "TP2") (pin "TP") (pinfunction "TP_TP") (pintype "passive"))
    )
    (net (code "6") (name "/PME_N{slash}CONNECT") (class "Default")
      (node (ref "IC2") (pin "22") (pinfunction "PME_N/GPIO4_22") (pintype "passive"))
      (node (ref "R10") (pin "2") (pinfunction "2_2") (pintype "passive"))
    )
    (net (code "7") (name "/TEST") (class "Default")
      (node (ref "IC2") (pin "34") (pinfunction "TEST_34") (pintype "passive"))
      (node (ref "R12") (pin "2") (pinfunction "2_2") (pintype "passive"))
    )
    (net (code "8") (name "/TR0_N") (class "Default")
      (node (ref "D6") (pin "9") (pinfunction "I/O_8_9") (pintype "passive"))
      (node (ref "IC2") (pin "2") (pinfunction "TR0N_2") (pintype "passive"))
      (node (ref "X2") (pin "P2") (pinfunction "D1-_P2") (pintype "passive"))
    )
    (net (code "9") (name "/TR0_P") (class "Default")
      (node (ref "D6") (pin "1") (pinfunction "I/O_1_1") (pintype "passive"))
      (node (ref "IC2") (pin "1") (pinfunction "TR0P_1") (pintype "passive"))
      (node (ref "X2") (pin "P1") (pinfunction "D1+_P1") (pintype "passive"))
    )
    (net (code "10") (name "/TR1_N") (class "Default")
      (node (ref "D6") (pin "5") (pinfunction "I/O_4_5") (pintype "passive"))
      (node (ref "IC2") (pin "5") (pinfunction "TR1N_5") (pintype "passive"))
      (node (ref "X2") (pin "P6") (pinfunction "D2-_P6") (pintype "passive"))
    )
    (net (code "11") (name "/TR1_P") (class "Default")
      (node (ref "D6") (pin "6") (pinfunction "I/O_5_6") (pintype "passive"))
      (node (ref "IC2") (pin "4") (pinfunction "TR1P_4") (pintype "passive"))
      (node (ref "X2") (pin "P3") (pinfunction "D2+_P3") (pintype "passive"))
    )
    (net (code "12") (name "/TR2_N") (class "Default")
      (node (ref "D7") (pin "9") (pinfunction "I/O_8_9") (pintype "passive"))
      (node (ref "IC2") (pin "8") (pinfunction "TR2N_8") (pintype "passive"))
      (node (ref "X2") (pin "P5") (pinfunction "D3-_P5") (pintype "passive"))
    )
    (net (code "13") (name "/TR2_P") (class "Default")
      (node (ref "D7") (pin "1") (pinfunction "I/O_1_1") (pintype "passive"))
      (node (ref "IC2") (pin "7") (pinfunction "TR2P_7") (pintype "passive"))
      (node (ref "X2") (pin "P4") (pinfunction "D3+_P4") (pintype "passive"))
    )
    (net (code "14") (name "/TR3_N") (class "Default")
      (node (ref "D7") (pin "5") (pinfunction "I/O_4_5") (pintype "passive"))
      (node (ref "IC2") (pin "11") (pinfunction "TR3N_11") (pintype "passive"))
      (node (ref "X2") (pin "P8") (pinfunction "D4-_P8") (pintype "passive"))
    )
    (net (code "15") (name "/TR3_P") (class "Default")
      (node (ref "D7") (pin "6") (pinfunction "I/O_5_6") (pintype "passive"))
      (node (ref "IC2") (pin "10") (pinfunction "TR3P_10") (pintype "passive"))
      (node (ref "X2") (pin "P7") (pinfunction "D4+_P7") (pintype "passive"))
    )
    (net (code "16") (name "/USB2D1_N") (class "Default")
      (node (ref "D5") (pin "2") (pinfunction "I/O_2_2") (pintype "passive"))
      (node (ref "D5") (pin "5") (pinfunction "NC_5") (pintype "passive"))
      (node (ref "L5") (pin "4") (pinfunction "4_4") (pintype "passive"))
      (node (ref "X1") (pin "A7") (pinfunction "D-_A7") (pintype "passive"))
      (node (ref "X1") (pin "B7") (pinfunction "D-_B7") (pintype "passive"))
    )
    (net (code "17") (name "/USB2D1_P") (class "Default")
      (node (ref "D5") (pin "1") (pinfunction "I/O_1_1") (pintype "passive"))
      (node (ref "D5") (pin "6") (pinfunction "NC_6") (pintype "passive"))
      (node (ref "L5") (pin "1") (pinfunction "1_1") (pintype "passive"))
      (node (ref "X1") (pin "A6") (pinfunction "D+_A6") (pintype "passive"))
      (node (ref "X1") (pin "B6") (pinfunction "D+_B6") (pintype "passive"))
    )
    (net (code "18") (name "/USB2D_N") (class "Default")
      (node (ref "IC2") (pin "27") (pinfunction "USB2_DM_27") (pintype "passive"))
      (node (ref "L5") (pin "3") (pinfunction "3_3") (pintype "passive"))
    )
    (net (code "19") (name "/USB2D_P") (class "Default")
      (node (ref "IC2") (pin "26") (pinfunction "USB2_DP_26") (pintype "passive"))
      (node (ref "L5") (pin "2") (pinfunction "2_2") (pintype "passive"))
    )
    (net (code "20") (name "/USB3RX1_N") (class "Default")
      (node (ref "D4") (pin "2") (pinfunction "I/O_2_2") (pintype "passive"))
      (node (ref "D4") (pin "5") (pinfunction "NC_5") (pintype "passive"))
      (node (ref "L3") (pin "4") (pinfunction "4_4") (pintype "passive"))
      (node (ref "X1") (pin "B11") (pinfunction "SSRXp1_B11") (pintype "passive"))
    )
    (net (code "21") (name "/USB3RX1_P") (class "Default")
      (node (ref "D4") (pin "1") (pinfunction "I/O_1_1") (pintype "passive"))
      (node (ref "D4") (pin "6") (pinfunction "NC_6") (pintype "passive"))
      (node (ref "L3") (pin "1") (pinfunction "1_1") (pintype "passive"))
      (node (ref "X1") (pin "B10") (pinfunction "SSRXn1_B10") (pintype "passive"))
    )
    (net (code "22") (name "/USB3RX_N") (class "Default")
      (node (ref "IC2") (pin "32") (pinfunction "USB3_RXDM_32") (pintype "passive"))
      (node (ref "L3") (pin "3") (pinfunction "3_3") (pintype "passive"))
    )
    (net (code "23") (name "/USB3RX_P") (class "Default")
      (node (ref "IC2") (pin "31") (pinfunction "USB3_RXDP_31") (pintype "passive"))
      (node (ref "L3") (pin "2") (pinfunction "2_2") (pintype "passive"))
    )
    (net (code "24") (name "/USB3TX1_N") (class "Default")
      (node (ref "D1") (pin "2") (pinfunction "I/O_2_2") (pintype "passive"))
      (node (ref "D1") (pin "5") (pinfunction "NC_5") (pintype "passive"))
      (node (ref "L2") (pin "4") (pinfunction "4_4") (pintype "passive"))
      (node (ref "X1") (pin "A3") (pinfunction "SSTXn1_A3") (pintype "passive"))
    )
    (net (code "25") (name "/USB3TX1_P") (class "Default")
      (node (ref "D1") (pin "1") (pinfunction "I/O_1_1") (pintype "passive"))
      (node (ref "D1") (pin "6") (pinfunction "NC_6") (pintype "passive"))
      (node (ref "L2") (pin "1") (pinfunction "1_1") (pintype "passive"))
      (node (ref "X1") (pin "A2") (pinfunction "SSTXp1_A2") (pintype "passive"))
    )
    (net (code "26") (name "/USB3TX2_N") (class "Default")
      (node (ref "C5") (pin "1") (pinfunction "1_1") (pintype "passive"))
      (node (ref "L2") (pin "3") (pinfunction "3_3") (pintype "passive"))
    )
    (net (code "27") (name "/USB3TX2_P") (class "Default")
      (node (ref "C2") (pin "1") (pinfunction "1_1") (pintype "passive"))
      (node (ref "L2") (pin "2") (pinfunction "2_2") (pintype "passive"))
    )
    (net (code "28") (name "/USB3TX_N") (class "Default")
      (node (ref "C5") (pin "2") (pinfunction "2_2") (pintype "passive"))
      (node (ref "IC2") (pin "29") (pinfunction "USB3_TXDM_29") (pintype "passive"))
    )
    (net (code "29") (name "/USB3TX_P") (class "Default")
      (node (ref "C2") (pin "2") (pinfunction "2_2") (pintype "passive"))
      (node (ref "IC2") (pin "28") (pinfunction "USB3_TXDP_28") (pintype "passive"))
    )
    (net (code "30") (name "/USERBIAS") (class "Default")
      (node (ref "IC2") (pin "37") (pinfunction "USBRBIAS_37") (pintype "passive"))
      (node (ref "R11") (pin "2") (pinfunction "2_2") (pintype "passive"))
    )
    (net (code "31") (name "/VBUS") (class "Default")
      (node (ref "C9") (pin "2") (pinfunction "2_2") (pintype "passive"))
      (node (ref "FB2") (pin "2") (pinfunction "2_2") (pintype "passive"))
      (node (ref "X1") (pin "A4") (pinfunction "VBUS_A4") (pintype "passive"))
      (node (ref "X1") (pin "A9") (pinfunction "VBUS_A9") (pintype "passive"))
      (node (ref "X1") (pin "B4") (pinfunction "VBUS_B4") (pintype "passive"))
      (node (ref "X1") (pin "B9") (pinfunction "VBUS_B9") (pintype "passive"))
    )
    (net (code "32") (name "/VDD12_SW_OUT") (class "Default")
      (node (ref "IC2") (pin "13") (pinfunction "VDD12_SW_OUT_13") (pintype "passive"))
      (node (ref "L4") (pin "1") (pinfunction "1_1") (pintype "passive"))
    )
    (net (code "33") (name "GND") (class "Default")
      (node (ref "C1") (pin "1") (pinfunction "1_1") (pintype "passive"))
      (node (ref "C10") (pin "2") (pinfunction "2_2") (pintype "passive"))
      (node (ref "C11") (pin "1") (pinfunction "1_1") (pintype "passive"))
      (node (ref "C12") (pin "1") (pinfunction "1_1") (pintype "passive"))
      (node (ref "C13") (pin "1") (pinfunction "1_1") (pintype "passive"))
      (node (ref "C14") (pin "1") (pinfunction "1_1") (pintype "passive"))
      (node (ref "C15") (pin "1") (pinfunction "1_1") (pintype "passive"))
      (node (ref "C16") (pin "1") (pinfunction "1_1") (pintype "passive"))
      (node (ref "C17") (pin "1") (pinfunction "1_1") (pintype "passive"))
      (node (ref "C18") (pin "2") (pinfunction "2_2") (pintype "passive"))
      (node (ref "C19") (pin "1") (pinfunction "1_1") (pintype "passive"))
      (node (ref "C20") (pin "2") (pinfunction "2_2") (pintype "passive"))
      (node (ref "C22") (pin "1") (pinfunction "1_1") (pintype "passive"))
      (node (ref "C23") (pin "1") (pinfunction "1_1") (pintype "passive"))
      (node (ref "C24") (pin "1") (pinfunction "1_1") (pintype "passive"))
      (node (ref "C25") (pin "1") (pinfunction "1_1") (pintype "passive"))
      (node (ref "C26") (pin "1") (pinfunction "1_1") (pintype "passive"))
      (node (ref "C27") (pin "1") (pinfunction "1_1") (pintype "passive"))
      (node (ref "C28") (pin "1") (pinfunction "1_1") (pintype "passive"))
      (node (ref "C29") (pin "1") (pinfunction "1_1") (pintype "passive"))
      (node (ref "C3") (pin "1") (pinfunction "1_1") (pintype "passive"))
      (node (ref "C30") (pin "1") (pinfunction "1_1") (pintype "passive"))
      (node (ref "C31") (pin "1") (pinfunction "1_1") (pintype "passive"))
      (node (ref "C32") (pin "1") (pinfunction "1_1") (pintype "passive"))
      (node (ref "C33") (pin "1") (pinfunction "1_1") (pintype "passive"))
      (node (ref "C34") (pin "1") (pinfunction "1_1") (pintype "passive"))
      (node (ref "C35") (pin "1") (pinfunction "1_1") (pintype "passive"))
      (node (ref "C36") (pin "1") (pinfunction "1_1") (pintype "passive"))
      (node (ref "C37") (pin "1") (pinfunction "1_1") (pintype "passive"))
      (node (ref "C38") (pin "1") (pinfunction "1_1") (pintype "passive"))
      (node (ref "C39") (pin "1") (pinfunction "1_1") (pintype "passive"))
      (node (ref "C4") (pin "1") (pinfunction "1_1") (pintype "passive"))
      (node (ref "C40") (pin "1") (pinfunction "1_1") (pintype "passive"))
      (node (ref "C41") (pin "1") (pinfunction "1_1") (pintype "passive"))
      (node (ref "C42") (pin "1") (pinfunction "1_1") (pintype "passive"))
      (node (ref "C43") (pin "1") (pinfunction "1_1") (pintype "passive"))
      (node (ref "C44") (pin "1") (pinfunction "1_1") (pintype "passive"))
      (node (ref "C45") (pin "1") (pinfunction "1_1") (pintype "passive"))
      (node (ref "C46") (pin "1") (pinfunction "1_1") (pintype "passive"))
      (node (ref "C6") (pin "1") (pinfunction "1_1") (pintype "passive"))
      (node (ref "C7") (pin "1") (pinfunction "1_1") (pintype "passive"))
      (node (ref "C8") (pin "1") (pinfunction "1_1") (pintype "passive"))
      (node (ref "D1") (pin "3") (pinfunction "GND_3") (pintype "passive"))
      (node (ref "D2") (pin "1") (pinfunction "CATHODE_1") (pintype "passive"))
      (node (ref "D3") (pin "2") (pinfunction "GND_2") (pintype "passive"))
      (node (ref "D4") (pin "3") (pinfunction "GND_3") (pintype "passive"))
      (node (ref "D5") (pin "3") (pinfunction "GND_3") (pintype "passive"))
      (node (ref "D6") (pin "3") (pinfunction "GND_3") (pintype "passive"))
      (node (ref "D7") (pin "3") (pinfunction "GND_3") (pintype "passive"))
      (node (ref "IC1") (pin "2") (pinfunction "GND_2") (pintype "passive"))
      (node (ref "IC2") (pin "49") (pinfunction "VSS(FLAG)_49") (pintype "passive"))
      (node (ref "IC3") (pin "5") (pinfunction "VSS_5") (pintype "passive"))
      (node (ref "R11") (pin "1") (pinfunction "1_1") (pintype "passive"))
      (node (ref "R12") (pin "1") (pinfunction "1_1") (pintype "passive"))
      (node (ref "R13") (pin "1") (pinfunction "1_1") (pintype "passive"))
      (node (ref "R14") (pin "1") (pinfunction "1_1") (pintype "passive"))
      (node (ref "R15") (pin "1") (pinfunction "1_1") (pintype "passive"))
      (node (ref "R16") (pin "2") (pinfunction "2_2") (pintype "passive"))
      (node (ref "R17") (pin "2") (pinfunction "2_2") (pintype "passive"))
      (node (ref "R18") (pin "2") (pinfunction "2_2") (pintype "passive"))
      (node (ref "R19") (pin "2") (pinfunction "2_2") (pintype "passive"))
      (node (ref "R20") (pin "1") (pinfunction "1_1") (pintype "passive"))
      (node (ref "R21") (pin "1") (pinfunction "1_1") (pintype "passive"))
      (node (ref "R22") (pin "1") (pinfunction "1_1") (pintype "passive"))
      (node (ref "R3") (pin "2") (pinfunction "2_2") (pintype "passive"))
      (node (ref "R4") (pin "1") (pinfunction "1_1") (pintype "passive"))
      (node (ref "R9") (pin "2") (pinfunction "2_2") (pintype "passive"))
      (node (ref "X1") (pin "A1") (pinfunction "GND_A1") (pintype "passive"))
      (node (ref "X1") (pin "A12") (pinfunction "GND_A12") (pintype "passive"))
      (node (ref "X1") (pin "B1") (pinfunction "GND_B1") (pintype "passive"))
      (node (ref "X1") (pin "B12") (pinfunction "GND_B12") (pintype "passive"))
      (node (ref "Y1") (pin "2") (pinfunction "GND_2") (pintype "passive"))
      (node (ref "Y1") (pin "4") (pinfunction "GND_4") (pintype "passive"))
    )
    (net (code "34") (name "Net-(C7-Pad2)") (class "Default")
      (node (ref "C7") (pin "2") (pinfunction "2_2") (pintype "passive"))
      (node (ref "FB1") (pin "2") (pinfunction "2_2") (pintype "passive"))
      (node (ref "L1") (pin "1") (pinfunction "1_1") (pintype "passive"))
    )
    (net (code "35") (name "Net-(C8-Pad2)") (class "Default")
      (node (ref "C8") (pin "2") (pinfunction "2_2") (pintype "passive"))
      (node (ref "FB2") (pin "1") (pinfunction "1_1") (pintype "passive"))
      (node (ref "L1") (pin "2") (pinfunction "2_2") (pintype "passive"))
    )
    (net (code "36") (name "Net-(C15-Pad2)") (class "Default")
      (node (ref "C15") (pin "2") (pinfunction "2_2") (pintype "passive"))
      (node (ref "FB3") (pin "1") (pinfunction "1_1") (pintype "passive"))
      (node (ref "IC2") (pin "25") (pinfunction "VDD12A_25") (pintype "passive"))
    )
    (net (code "37") (name "Net-(D2-ANODE)") (class "Default")
      (node (ref "D2") (pin "2") (pinfunction "ANODE_2") (pintype "passive"))
      (node (ref "R1") (pin "1") (pinfunction "1_1") (pintype "passive"))
    )
    (net (code "38") (name "Net-(IC1-EN)") (class "Default")
      (node (ref "C6") (pin "2") (pinfunction "2_2") (pintype "passive"))
      (node (ref "IC1") (pin "3") (pinfunction "EN_3") (pintype "passive"))
      (node (ref "R2") (pin "1") (pinfunction "1_1") (pintype "passive"))
    )
    (net (code "39") (name "Net-(IC2A-EECLK{slash}LED1{slash}GPIO3)") (class "Default")
      (node (ref "IC2") (pin "19") (pinfunction "EECLK/LED1/GPIO3_19") (pintype "passive"))
      (node (ref "IC3") (pin "2") (pinfunction "CLK_2") (pintype "passive"))
    )
    (net (code "40") (name "Net-(IC2A-EECS{slash}GPIO0)") (class "Default")
      (node (ref "IC2") (pin "16") (pinfunction "EECS/GPIO0_16") (pintype "passive"))
      (node (ref "IC3") (pin "1") (pinfunction "CS_1") (pintype "passive"))
      (node (ref "R13") (pin "2") (pinfunction "2_2") (pintype "passive"))
    )
    (net (code "41") (name "Net-(IC2A-EEDI{slash}GPIO1)") (class "Default")
      (node (ref "IC2") (pin "17") (pinfunction "EEDI/GPIO1_17") (pintype "passive"))
      (node (ref "IC3") (pin "4") (pinfunction "DO_4") (pintype "passive"))
    )
    (net (code "42") (name "Net-(IC2A-EEDO{slash}LED0{slash}GPIO2)") (class "Default")
      (node (ref "IC2") (pin "18") (pinfunction "EEDO/LED0/GPIO2_18") (pintype "passive"))
      (node (ref "IC3") (pin "3") (pinfunction "DI_3") (pintype "passive"))
    )
    (net (code "43") (name "Net-(IC2A-REF_FILT)") (class "Default")
      (node (ref "C19") (pin "2") (pinfunction "2_2") (pintype "passive"))
      (node (ref "IC2") (pin "48") (pinfunction "REF_FILT_48") (pintype "passive"))
    )
    (net (code "44") (name "Net-(IC2A-REF_REXT)") (class "Default")
      (node (ref "IC2") (pin "47") (pinfunction "REF_REXT_47") (pintype "passive"))
      (node (ref "R9") (pin "1") (pinfunction "1_1") (pintype "passive"))
    )
    (net (code "45") (name "Net-(IC2A-RESET_N{slash}PME_CLEAR)") (class "Default")
      (node (ref "IC2") (pin "35") (pinfunction "RESET_N/PME_CLEAR_35") (pintype "passive"))
      (node (ref "R6") (pin "1") (pinfunction "1_1") (pintype "passive"))
    )
    (net (code "46") (name "Net-(IC2A-VBUS_DET)") (class "Default")
      (node (ref "IC2") (pin "23") (pinfunction "VBUS_DET_23") (pintype "passive"))
      (node (ref "R5") (pin "1") (pinfunction "1_1") (pintype "passive"))
    )
    (net (code "47") (name "Net-(IC2A-XI)") (class "Default")
      (node (ref "C18") (pin "1") (pinfunction "1_1") (pintype "passive"))
      (node (ref "IC2") (pin "40") (pinfunction "XI_40") (pintype "passive"))
      (node (ref "Y1") (pin "1") (pinfunction "1_1") (pintype "passive"))
    )
    (net (code "48") (name "Net-(IC2A-XO)") (class "Default")
      (node (ref "C20") (pin "1") (pinfunction "1_1") (pintype "passive"))
      (node (ref "IC2") (pin "41") (pinfunction "XO_41") (pintype "passive"))
      (node (ref "Y1") (pin "3") (pinfunction "3_3") (pintype "passive"))
    )
    (net (code "49") (name "Net-(IC3-ORG)") (class "Default")
      (node (ref "IC3") (pin "6") (pinfunction "ORG_6") (pintype "passive"))
      (node (ref "R14") (pin "2") (pinfunction "2_2") (pintype "passive"))
    )
    (net (code "50") (name "Net-(X1-CC1)") (class "Default")
      (node (ref "R4") (pin "2") (pinfunction "2_2") (pintype "passive"))
      (node (ref "X1") (pin "A5") (pinfunction "CC1_A5") (pintype "passive"))
    )
    (net (code "51") (name "Net-(X2-11)") (class "Default")
      (node (ref "R7") (pin "2") (pinfunction "2_2") (pintype "passive"))
      (node (ref "X2") (pin "P11") (pinfunction "11_P11") (pintype "passive"))
    )
    (net (code "52") (name "Net-(X2-13)") (class "Default")
      (node (ref "R8") (pin "2") (pinfunction "2_2") (pintype "passive"))
      (node (ref "X2") (pin "P13") (pinfunction "13_P13") (pintype "passive"))
    )
    (net (code "53") (name "PHY_AVDD") (class "Default")
      (node (ref "TP1") (pin "TP") (pinfunction "TP_TP") (pintype "passive"))
      (node (ref "X2") (pin "P9") (pinfunction "VCC_P9") (pintype "passive"))
    )
    (net (code "54") (name "SHIELD") (class "Default")
      (node (ref "C21") (pin "1") (pinfunction "1_1") (pintype "passive"))
      (node (ref "C22") (pin "2") (pinfunction "2_2") (pintype "passive"))
      (node (ref "C23") (pin "2") (pinfunction "2_2") (pintype "passive"))
      (node (ref "C24") (pin "2") (pinfunction "2_2") (pintype "passive"))
      (node (ref "C25") (pin "2") (pinfunction "2_2") (pintype "passive"))
      (node (ref "C26") (pin "2") (pinfunction "2_2") (pintype "passive"))
      (node (ref "C27") (pin "2") (pinfunction "2_2") (pintype "passive"))
      (node (ref "H1") (pin "H") (pinfunction "H_H") (pintype "passive"))
      (node (ref "H4") (pin "H") (pinfunction "H_H") (pintype "passive"))
      (node (ref "R15") (pin "2") (pinfunction "2_2") (pintype "passive"))
      (node (ref "R22") (pin "2") (pinfunction "2_2") (pintype "passive"))
      (node (ref "X2") (pin "P10") (pinfunction "GND_P10") (pintype "passive"))
      (node (ref "X2") (pin "S1") (pinfunction "S1_S1") (pintype "passive"))
      (node (ref "X2") (pin "S2") (pinfunction "S2_S2") (pintype "passive"))
    )
    (net (code "55") (name "SHIELD_USB") (class "Default")
      (node (ref "C10") (pin "1") (pinfunction "1_1") (pintype "passive"))
      (node (ref "C9") (pin "1") (pinfunction "1_1") (pintype "passive"))
      (node (ref "H2") (pin "H") (pinfunction "H_H") (pintype "passive"))
      (node (ref "H3") (pin "H") (pinfunction "H_H") (pintype "passive"))
      (node (ref "R16") (pin "1") (pinfunction "1_1") (pintype "passive"))
      (node (ref "R17") (pin "1") (pinfunction "1_1") (pintype "passive"))
      (node (ref "R18") (pin "1") (pinfunction "1_1") (pintype "passive"))
      (node (ref "R19") (pin "1") (pinfunction "1_1") (pintype "passive"))
      (node (ref "R20") (pin "2") (pinfunction "2_2") (pintype "passive"))
      (node (ref "R21") (pin "2") (pinfunction "2_2") (pintype "passive"))
      (node (ref "R3") (pin "1") (pinfunction "1_1") (pintype "passive"))
      (node (ref "X1") (pin "SH1") (pinfunction "SH1_SH1") (pintype "passive"))
      (node (ref "X1") (pin "SH2") (pinfunction "SH2_SH2") (pintype "passive"))
      (node (ref "X1") (pin "SH3") (pinfunction "SH3_SH3") (pintype "passive"))
      (node (ref "X1") (pin "SH4") (pinfunction "SH4_SH4") (pintype "passive"))
    )
    (net (code "56") (name "VDD12") (class "Default")
      (node (ref "C11") (pin "2") (pinfunction "2_2") (pintype "passive"))
      (node (ref "C12") (pin "2") (pinfunction "2_2") (pintype "passive"))
      (node (ref "C35") (pin "2") (pinfunction "2_2") (pintype "passive"))
      (node (ref "C36") (pin "2") (pinfunction "2_2") (pintype "passive"))
      (node (ref "C37") (pin "2") (pinfunction "2_2") (pintype "passive"))
      (node (ref "C38") (pin "2") (pinfunction "2_2") (pintype "passive"))
      (node (ref "C39") (pin "2") (pinfunction "2_2") (pintype "passive"))
      (node (ref "C40") (pin "2") (pinfunction "2_2") (pintype "passive"))
      (node (ref "FB3") (pin "2") (pinfunction "2_2") (pintype "passive"))
      (node (ref "IC2") (pin "15") (pinfunction "VDD12_SW_FB_15") (pintype "passive"))
      (node (ref "IC2") (pin "21") (pinfunction "VDD12CORE_21") (pintype "passive"))
      (node (ref "IC2") (pin "30") (pinfunction "VDD12A_30") (pintype "passive"))
      (node (ref "IC2") (pin "42") (pinfunction "VDD12CORE_42") (pintype "passive"))
      (node (ref "IC2") (pin "44") (pinfunction "VDD12A_44") (pintype "passive"))
      (node (ref "L4") (pin "2") (pinfunction "2_2") (pintype "passive"))
    )
    (net (code "57") (name "VDD25") (class "Default")
      (node (ref "C16") (pin "2") (pinfunction "2_2") (pintype "passive"))
      (node (ref "C29") (pin "2") (pinfunction "2_2") (pintype "passive"))
      (node (ref "C30") (pin "2") (pinfunction "2_2") (pintype "passive"))
      (node (ref "C31") (pin "2") (pinfunction "2_2") (pintype "passive"))
      (node (ref "C32") (pin "2") (pinfunction "2_2") (pintype "passive"))
      (node (ref "C33") (pin "2") (pinfunction "2_2") (pintype "passive"))
      (node (ref "C34") (pin "2") (pinfunction "2_2") (pintype "passive"))
      (node (ref "IC2") (pin "12") (pinfunction "VDD25A_12") (pintype "passive"))
      (node (ref "IC2") (pin "3") (pinfunction "VDD25A_3") (pintype "passive"))
      (node (ref "IC2") (pin "45") (pinfunction "VDD25_REG_OUT_45") (pintype "passive"))
      (node (ref "IC2") (pin "6") (pinfunction "VDD25A_6") (pintype "passive"))
      (node (ref "IC2") (pin "9") (pinfunction "VDD25A_9") (pintype "passive"))
    )
    (net (code "58") (name "unconnected-(D1-NC-Pad4)") (class "Default")
      (node (ref "D1") (pin "4") (pinfunction "NC_4") (pintype "passive+no_connect"))
    )
    (net (code "59") (name "unconnected-(D4-NC-Pad4)") (class "Default")
      (node (ref "D4") (pin "4") (pinfunction "NC_4") (pintype "passive+no_connect"))
    )
    (net (code "60") (name "unconnected-(D5-NC-Pad4)") (class "Default")
      (node (ref "D5") (pin "4") (pinfunction "NC_4") (pintype "passive+no_connect"))
    )
    (net (code "61") (name "unconnected-(D6-I{slash}O_2-Pad2)") (class "Default")
      (node (ref "D6") (pin "2") (pinfunction "I/O_2_2") (pintype "passive+no_connect"))
    )
    (net (code "62") (name "unconnected-(D6-I{slash}O_3-Pad4)") (class "Default")
      (node (ref "D6") (pin "4") (pinfunction "I/O_3_4") (pintype "passive+no_connect"))
    )
    (net (code "63") (name "unconnected-(D6-I{slash}O_6-Pad7)") (class "Default")
      (node (ref "D6") (pin "7") (pinfunction "I/O_6_7") (pintype "passive+no_connect"))
    )
    (net (code "64") (name "unconnected-(D6-I{slash}O_7-Pad8)") (class "Default")
      (node (ref "D6") (pin "8") (pinfunction "I/O_7_8") (pintype "passive+no_connect"))
    )
    (net (code "65") (name "unconnected-(D7-I{slash}O_2-Pad2)") (class "Default")
      (node (ref "D7") (pin "2") (pinfunction "I/O_2_2") (pintype "passive+no_connect"))
    )
    (net (code "66") (name "unconnected-(D7-I{slash}O_3-Pad4)") (class "Default")
      (node (ref "D7") (pin "4") (pinfunction "I/O_3_4") (pintype "passive+no_connect"))
    )
    (net (code "67") (name "unconnected-(D7-I{slash}O_6-Pad7)") (class "Default")
      (node (ref "D7") (pin "7") (pinfunction "I/O_6_7") (pintype "passive+no_connect"))
    )
    (net (code "68") (name "unconnected-(D7-I{slash}O_7-Pad8)") (class "Default")
      (node (ref "D7") (pin "8") (pinfunction "I/O_7_8") (pintype "passive+no_connect"))
    )
    (net (code "69") (name "unconnected-(IC1-NC-Pad4)") (class "Default")
      (node (ref "IC1") (pin "4") (pinfunction "NC_4") (pintype "passive+no_connect"))
    )
    (net (code "70") (name "unconnected-(IC3-NC-Pad7)") (class "Default")
      (node (ref "IC3") (pin "7") (pinfunction "NC_7") (pintype "passive+no_connect"))
    )
    (net (code "71") (name "unconnected-(X1-CC2-PadB5)") (class "Default")
      (node (ref "X1") (pin "B5") (pinfunction "CC2_B5") (pintype "passive+no_connect"))
    )
    (net (code "72") (name "unconnected-(X1-SBU1-PadA8)") (class "Default")
      (node (ref "X1") (pin "A8") (pinfunction "SBU1_A8") (pintype "passive+no_connect"))
    )
    (net (code "73") (name "unconnected-(X1-SBU2-PadB8)") (class "Default")
      (node (ref "X1") (pin "B8") (pinfunction "SBU2_B8") (pintype "passive+no_connect"))
    )
    (net (code "74") (name "unconnected-(X1-SSRXn2-PadA10)") (class "Default")
      (node (ref "X1") (pin "A10") (pinfunction "SSRXn2_A10") (pintype "passive+no_connect"))
    )
    (net (code "75") (name "unconnected-(X1-SSRXp2-PadA11)") (class "Default")
      (node (ref "X1") (pin "A11") (pinfunction "SSRXp2_A11") (pintype "passive+no_connect"))
    )
    (net (code "76") (name "unconnected-(X1-SSTXn2-PadB3)") (class "Default")
      (node (ref "X1") (pin "B3") (pinfunction "SSTXn2_B3") (pintype "passive+no_connect"))
    )
    (net (code "77") (name "unconnected-(X1-SSTXp2-PadB2)") (class "Default")
      (node (ref "X1") (pin "B2") (pinfunction "SSTXp2_B2") (pintype "passive+no_connect"))
    )
  )
)
